# driver_MC33887PFK.net
KiCad netlist of a schematic drawn in EAGLE
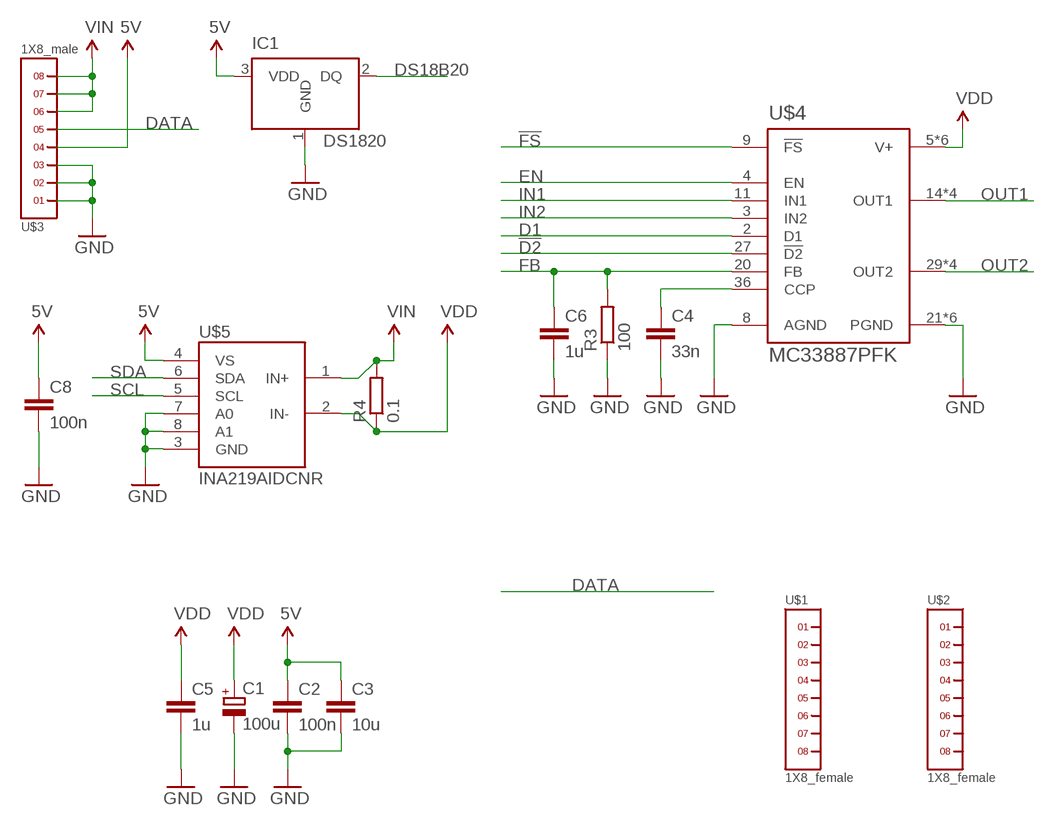
[diagram p0: schematic, sheet 1]

(export (version "E")
  (design (tool "Eeschema 10.0.6"))
  (components
    (comp (ref "C1")
      (value "100u")
      (footprint "eagle-import:PANASONIC_D")
      (libsource (lib "eagle-import") (part "CPOL-EUD"))
    )
    (comp (ref "C2")
      (value "100n")
      (footprint "eagle-import:C0402K")
      (libsource (lib "eagle-import") (part "C-EUC0402K"))
    )
    (comp (ref "C3")
      (value "10u")
      (footprint "eagle-import:C0603K")
      (libsource (lib "eagle-import") (part "C-EUC0603K"))
    )
    (comp (ref "C4")
      (value "33n")
      (footprint "eagle-import:C0402K")
      (libsource (lib "eagle-import") (part "C-EUC0402K"))
    )
    (comp (ref "C5")
      (value "1u")
      (footprint "eagle-import:C0402K")
      (libsource (lib "eagle-import") (part "C-EUC0402K"))
    )
    (comp (ref "C6")
      (value "1u")
      (footprint "eagle-import:C0402K")
      (libsource (lib "eagle-import") (part "C-EUC0402K"))
    )
    (comp (ref "C8")
      (value "100n")
      (footprint "eagle-import:C0402K")
      (libsource (lib "eagle-import") (part "C-EUC0402K"))
    )
    (comp (ref "IC1")
      (value "DS1820")
      (footprint "eagle-import:TO-92")
      (libsource (lib "eagle-import") (part "DS1820"))
    )
    (comp (ref "R3")
      (value "100")
      (footprint "eagle-import:R0402")
      (libsource (lib "eagle-import") (part "R-EU_R0402"))
    )
    (comp (ref "R4")
      (value "0.1")
      (footprint "eagle-import:R0603")
      (libsource (lib "eagle-import") (part "R-EU_R0603"))
    )
    (comp (ref "U$1")
      (value "1X8_female")
      (footprint "eagle-import:1X8")
      (libsource (lib "eagle-import") (part "1X8"))
    )
    (comp (ref "U$2")
      (value "1X8_female")
      (footprint "eagle-import:1X8")
      (libsource (lib "eagle-import") (part "1X8"))
    )
    (comp (ref "U$3")
      (value "1X8_male")
      (footprint "eagle-import:1X8_MALE")
      (libsource (lib "eagle-import") (part "1X8MALE"))
    )
    (comp (ref "U$4")
      (value "MC33887PFK")
      (footprint "eagle-import:QFN32")
      (libsource (lib "eagle-import") (part "MC33887"))
    )
    (comp (ref "U$5")
      (value "INA219AIDCNR")
      (footprint "eagle-import:SOT23-8L")
      (libsource (lib "eagle-import") (part "INA219AIDCNR"))
    )
  )
  (nets
    (net (code "1") (name "/D1") (class "Default")
      (node (ref "U$4") (pin "2") (pinfunction "D1_2") (pintype "input"))
    )
    (net (code "2") (name "/DATA") (class "Default")
      (node (ref "U$3") (pin "5") (pinfunction "5_5") (pintype "bidirectional"))
    )
    (net (code "3") (name "/DS18B20") (class "Default")
      (node (ref "IC1") (pin "2") (pinfunction "DQ_2") (pintype "output"))
    )
    (net (code "4") (name "/EN") (class "Default")
      (node (ref "U$4") (pin "4") (pinfunction "EN_4") (pintype "input"))
    )
    (net (code "5") (name "/FB") (class "Default")
      (node (ref "C6") (pin "1") (pinfunction "1_1") (pintype "passive"))
      (node (ref "R3") (pin "2") (pinfunction "2_2") (pintype "passive"))
      (node (ref "U$4") (pin "20") (pinfunction "FB_20") (pintype "output"))
    )
    (net (code "6") (name "/IN1") (class "Default")
      (node (ref "U$4") (pin "11") (pinfunction "IN1_11") (pintype "input"))
    )
    (net (code "7") (name "/IN2") (class "Default")
      (node (ref "U$4") (pin "3") (pinfunction "IN2_3") (pintype "input"))
    )
    (net (code "8") (name "/OUT1") (class "Default")
      (node (ref "U$4") (pin "14") (pinfunction "OUT1_14") (pintype "output"))
      (node (ref "U$4") (pin "15") (pinfunction "OUT1_15") (pintype "output"))
      (node (ref "U$4") (pin "17") (pinfunction "OUT1_17") (pintype "output"))
      (node (ref "U$4") (pin "18") (pinfunction "OUT1_18") (pintype "output"))
    )
    (net (code "9") (name "/OUT2") (class "Default")
      (node (ref "U$4") (pin "29") (pinfunction "OUT2_29") (pintype "output"))
      (node (ref "U$4") (pin "30") (pinfunction "OUT2_30") (pintype "output"))
      (node (ref "U$4") (pin "32") (pinfunction "OUT2_32") (pintype "output"))
      (node (ref "U$4") (pin "33") (pinfunction "OUT2_33") (pintype "output"))
    )
    (net (code "10") (name "/SCL") (class "Default")
      (node (ref "U$5") (pin "5") (pinfunction "SCL_5") (pintype "bidirectional"))
    )
    (net (code "11") (name "/SDA") (class "Default")
      (node (ref "U$5") (pin "6") (pinfunction "SDA_6") (pintype "bidirectional"))
    )
    (net (code "12") (name "/~{D2}") (class "Default")
      (node (ref "U$4") (pin "27") (pinfunction "~{D2}_27") (pintype "input"))
    )
    (net (code "13") (name "/~{FS}") (class "Default")
      (node (ref "U$4") (pin "9") (pinfunction "~{FS}_9") (pintype "output"))
    )
    (net (code "14") (name "5V") (class "Default")
      (node (ref "C2") (pin "1") (pinfunction "1_1") (pintype "passive"))
      (node (ref "C3") (pin "1") (pinfunction "1_1") (pintype "passive"))
      (node (ref "C8") (pin "1") (pinfunction "1_1") (pintype "passive"))
      (node (ref "IC1") (pin "3") (pinfunction "VDD_3") (pintype "input"))
      (node (ref "U$3") (pin "4") (pinfunction "4_4") (pintype "bidirectional"))
      (node (ref "U$5") (pin "4") (pinfunction "VS_4") (pintype "power_in"))
    )
    (net (code "15") (name "GND") (class "Default")
      (node (ref "C1") (pin "-") (pinfunction "-_-") (pintype "passive"))
      (node (ref "C2") (pin "2") (pinfunction "2_2") (pintype "passive"))
      (node (ref "C3") (pin "2") (pinfunction "2_2") (pintype "passive"))
      (node (ref "C4") (pin "2") (pinfunction "2_2") (pintype "passive"))
      (node (ref "C5") (pin "2") (pinfunction "2_2") (pintype "passive"))
      (node (ref "C6") (pin "2") (pinfunction "2_2") (pintype "passive"))
      (node (ref "C8") (pin "2") (pinfunction "2_2") (pintype "passive"))
      (node (ref "IC1") (pin "1") (pinfunction "GND_1") (pintype "power_in"))
      (node (ref "R3") (pin "1") (pinfunction "1_1") (pintype "passive"))
      (node (ref "U$3") (pin "1") (pinfunction "1_1") (pintype "bidirectional"))
      (node (ref "U$3") (pin "2") (pinfunction "2_2") (pintype "bidirectional"))
      (node (ref "U$3") (pin "3") (pinfunction "3_3") (pintype "bidirectional"))
      (node (ref "U$4") (pin "21") (pinfunction "PGND_21") (pintype "passive"))
      (node (ref "U$4") (pin "22") (pinfunction "PGND_22") (pintype "passive"))
      (node (ref "U$4") (pin "23") (pinfunction "PGND_23") (pintype "passive"))
      (node (ref "U$4") (pin "24") (pinfunction "PGND_24") (pintype "passive"))
      (node (ref "U$4") (pin "25") (pinfunction "PGND_25") (pintype "passive"))
      (node (ref "U$4") (pin "26") (pinfunction "PGND_26") (pintype "passive"))
      (node (ref "U$4") (pin "8") (pinfunction "AGND_8") (pintype "passive"))
      (node (ref "U$5") (pin "3") (pinfunction "GND_3") (pintype "power_in"))
      (node (ref "U$5") (pin "7") (pinfunction "A0_7") (pintype "input"))
      (node (ref "U$5") (pin "8") (pinfunction "A1_8") (pintype "input"))
    )
    (net (code "16") (name "Net-(U$4-CCP)") (class "Default")
      (node (ref "C4") (pin "1") (pinfunction "1_1") (pintype "passive"))
      (node (ref "U$4") (pin "36") (pinfunction "CCP_36") (pintype "passive"))
    )
    (net (code "17") (name "VDD") (class "Default")
      (node (ref "C1") (pin "+") (pinfunction "+_+") (pintype "passive"))
      (node (ref "C5") (pin "1") (pinfunction "1_1") (pintype "passive"))
      (node (ref "R4") (pin "1") (pinfunction "1_1") (pintype "passive"))
      (node (ref "U$4") (pin "12") (pinfunction "V+_12") (pintype "power_in"))
      (node (ref "U$4") (pin "13") (pinfunction "V+_13") (pintype "power_in"))
      (node (ref "U$4") (pin "34") (pinfunction "V+_34") (pintype "power_in"))
      (node (ref "U$4") (pin "35") (pinfunction "V+_35") (pintype "power_in"))
      (node (ref "U$4") (pin "5") (pinfunction "V+_5") (pintype "power_in"))
      (node (ref "U$4") (pin "6") (pinfunction "V+_6") (pintype "power_in"))
      (node (ref "U$5") (pin "2") (pinfunction "IN-_2") (pintype "input"))
    )
    (net (code "18") (name "VIN") (class "Default")
      (node (ref "R4") (pin "2") (pinfunction "2_2") (pintype "passive"))
      (node (ref "U$3") (pin "6") (pinfunction "6_6") (pintype "bidirectional"))
      (node (ref "U$3") (pin "7") (pinfunction "7_7") (pintype "bidirectional"))
      (node (ref "U$3") (pin "8") (pinfunction "8_8") (pintype "bidirectional"))
      (node (ref "U$5") (pin "1") (pinfunction "IN+_1") (pintype "input"))
    )
    (net (code "19") (name "unconnected-(U$1-Pad1)") (class "Default")
      (node (ref "U$1") (pin "1") (pinfunction "1_1") (pintype "bidirectional"))
    )
    (net (code "20") (name "unconnected-(U$1-Pad2)") (class "Default")
      (node (ref "U$1") (pin "2") (pinfunction "2_2") (pintype "bidirectional"))
    )
    (net (code "21") (name "unconnected-(U$1-Pad3)") (class "Default")
      (node (ref "U$1") (pin "3") (pinfunction "3_3") (pintype "bidirectional"))
    )
    (net (code "22") (name "unconnected-(U$1-Pad4)") (class "Default")
      (node (ref "U$1") (pin "4") (pinfunction "4_4") (pintype "bidirectional"))
    )
    (net (code "23") (name "unconnected-(U$1-Pad5)") (class "Default")
      (node (ref "U$1") (pin "5") (pinfunction "5_5") (pintype "bidirectional"))
    )
    (net (code "24") (name "unconnected-(U$1-Pad6)") (class "Default")
      (node (ref "U$1") (pin "6") (pinfunction "6_6") (pintype "bidirectional"))
    )
    (net (code "25") (name "unconnected-(U$1-Pad7)") (class "Default")
      (node (ref "U$1") (pin "7") (pinfunction "7_7") (pintype "bidirectional"))
    )
    (net (code "26") (name "unconnected-(U$1-Pad8)") (class "Default")
      (node (ref "U$1") (pin "8") (pinfunction "8_8") (pintype "bidirectional"))
    )
    (net (code "27") (name "unconnected-(U$2-Pad1)") (class "Default")
      (node (ref "U$2") (pin "1") (pinfunction "1_1") (pintype "bidirectional"))
    )
    (net (code "28") (name "unconnected-(U$2-Pad2)") (class "Default")
      (node (ref "U$2") (pin "2") (pinfunction "2_2") (pintype "bidirectional"))
    )
    (net (code "29") (name "unconnected-(U$2-Pad3)") (class "Default")
      (node (ref "U$2") (pin "3") (pinfunction "3_3") (pintype "bidirectional"))
    )
    (net (code "30") (name "unconnected-(U$2-Pad4)") (class "Default")
      (node (ref "U$2") (pin "4") (pinfunction "4_4") (pintype "bidirectional"))
    )
    (net (code "31") (name "unconnected-(U$2-Pad5)") (class "Default")
      (node (ref "U$2") (pin "5") (pinfunction "5_5") (pintype "bidirectional"))
    )
    (net (code "32") (name "unconnected-(U$2-Pad6)") (class "Default")
      (node (ref "U$2") (pin "6") (pinfunction "6_6") (pintype "bidirectional"))
    )
    (net (code "33") (name "unconnected-(U$2-Pad7)") (class "Default")
      (node (ref "U$2") (pin "7") (pinfunction "7_7") (pintype "bidirectional"))
    )
    (net (code "34") (name "unconnected-(U$2-Pad8)") (class "Default")
      (node (ref "U$2") (pin "8") (pinfunction "8_8") (pintype "bidirectional"))
    )
  )
)
